# Reset_Supervisor.net
KiCad netlist of a schematic drawn in Altium Designer
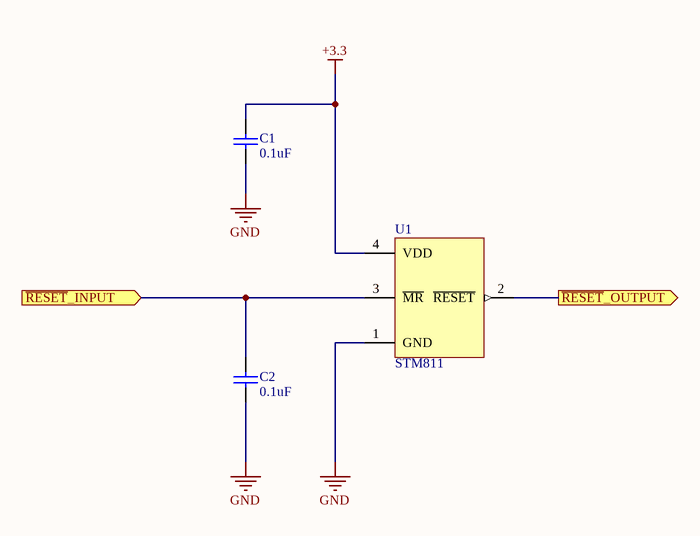
[diagram p0: Reset Supervisor.SchDoc]

(export (version "E")
  (design (tool "Eeschema 10.0.6"))
  (components
    (comp (ref "C1")
      (value "0.1uF")
      (footprint "C0603")
      (description "Capacitor")
      (fields (field (name "Comment") "Cap"))
      (libsource (lib "Miscellaneous Devices") (part "Cap"))
    )
    (comp (ref "C2")
      (value "0.1uF")
      (footprint "C0603")
      (description "Capacitor")
      (fields (field (name "Comment") "Cap"))
      (libsource (lib "Miscellaneous Devices") (part "Cap"))
    )
    (comp (ref "U1")
      (value "STM811")
      (footprint "STM811")
      (description "STMICROELECTRONICS - STM811TW16F - MPU LOW RESET 3.08V, SOT-143-4, 811")
      (libsource (lib "STM811") (part "STM811"))
    )
  )
  (nets
    (net (code "1") (name "+3.3") (class "Default")
      (node (ref "C1") (pin "1") (pinfunction "1_1") (pintype "passive"))
      (node (ref "U1") (pin "4") (pinfunction "VDD_4") (pintype "power_in"))
    )
    (net (code "2") (name "/~{RESET}_INPUT") (class "Default")
      (node (ref "C2") (pin "1") (pinfunction "1_1") (pintype "passive"))
      (node (ref "U1") (pin "3") (pinfunction "~{MR}_3") (pintype "passive"))
    )
    (net (code "3") (name "/~{RESET}_OUTPUT") (class "Default")
      (node (ref "U1") (pin "2") (pinfunction "~{RESET}_2") (pintype "output"))
    )
    (net (code "4") (name "GND") (class "Default")
      (node (ref "C1") (pin "2") (pinfunction "2_2") (pintype "passive"))
      (node (ref "C2") (pin "2") (pinfunction "2_2") (pintype "passive"))
      (node (ref "U1") (pin "1") (pinfunction "GND_1") (pintype "power_in"))
    )
  )
)
